# HotFire_BreakoutBoard.net
KiCad netlist of a schematic drawn in EAGLE
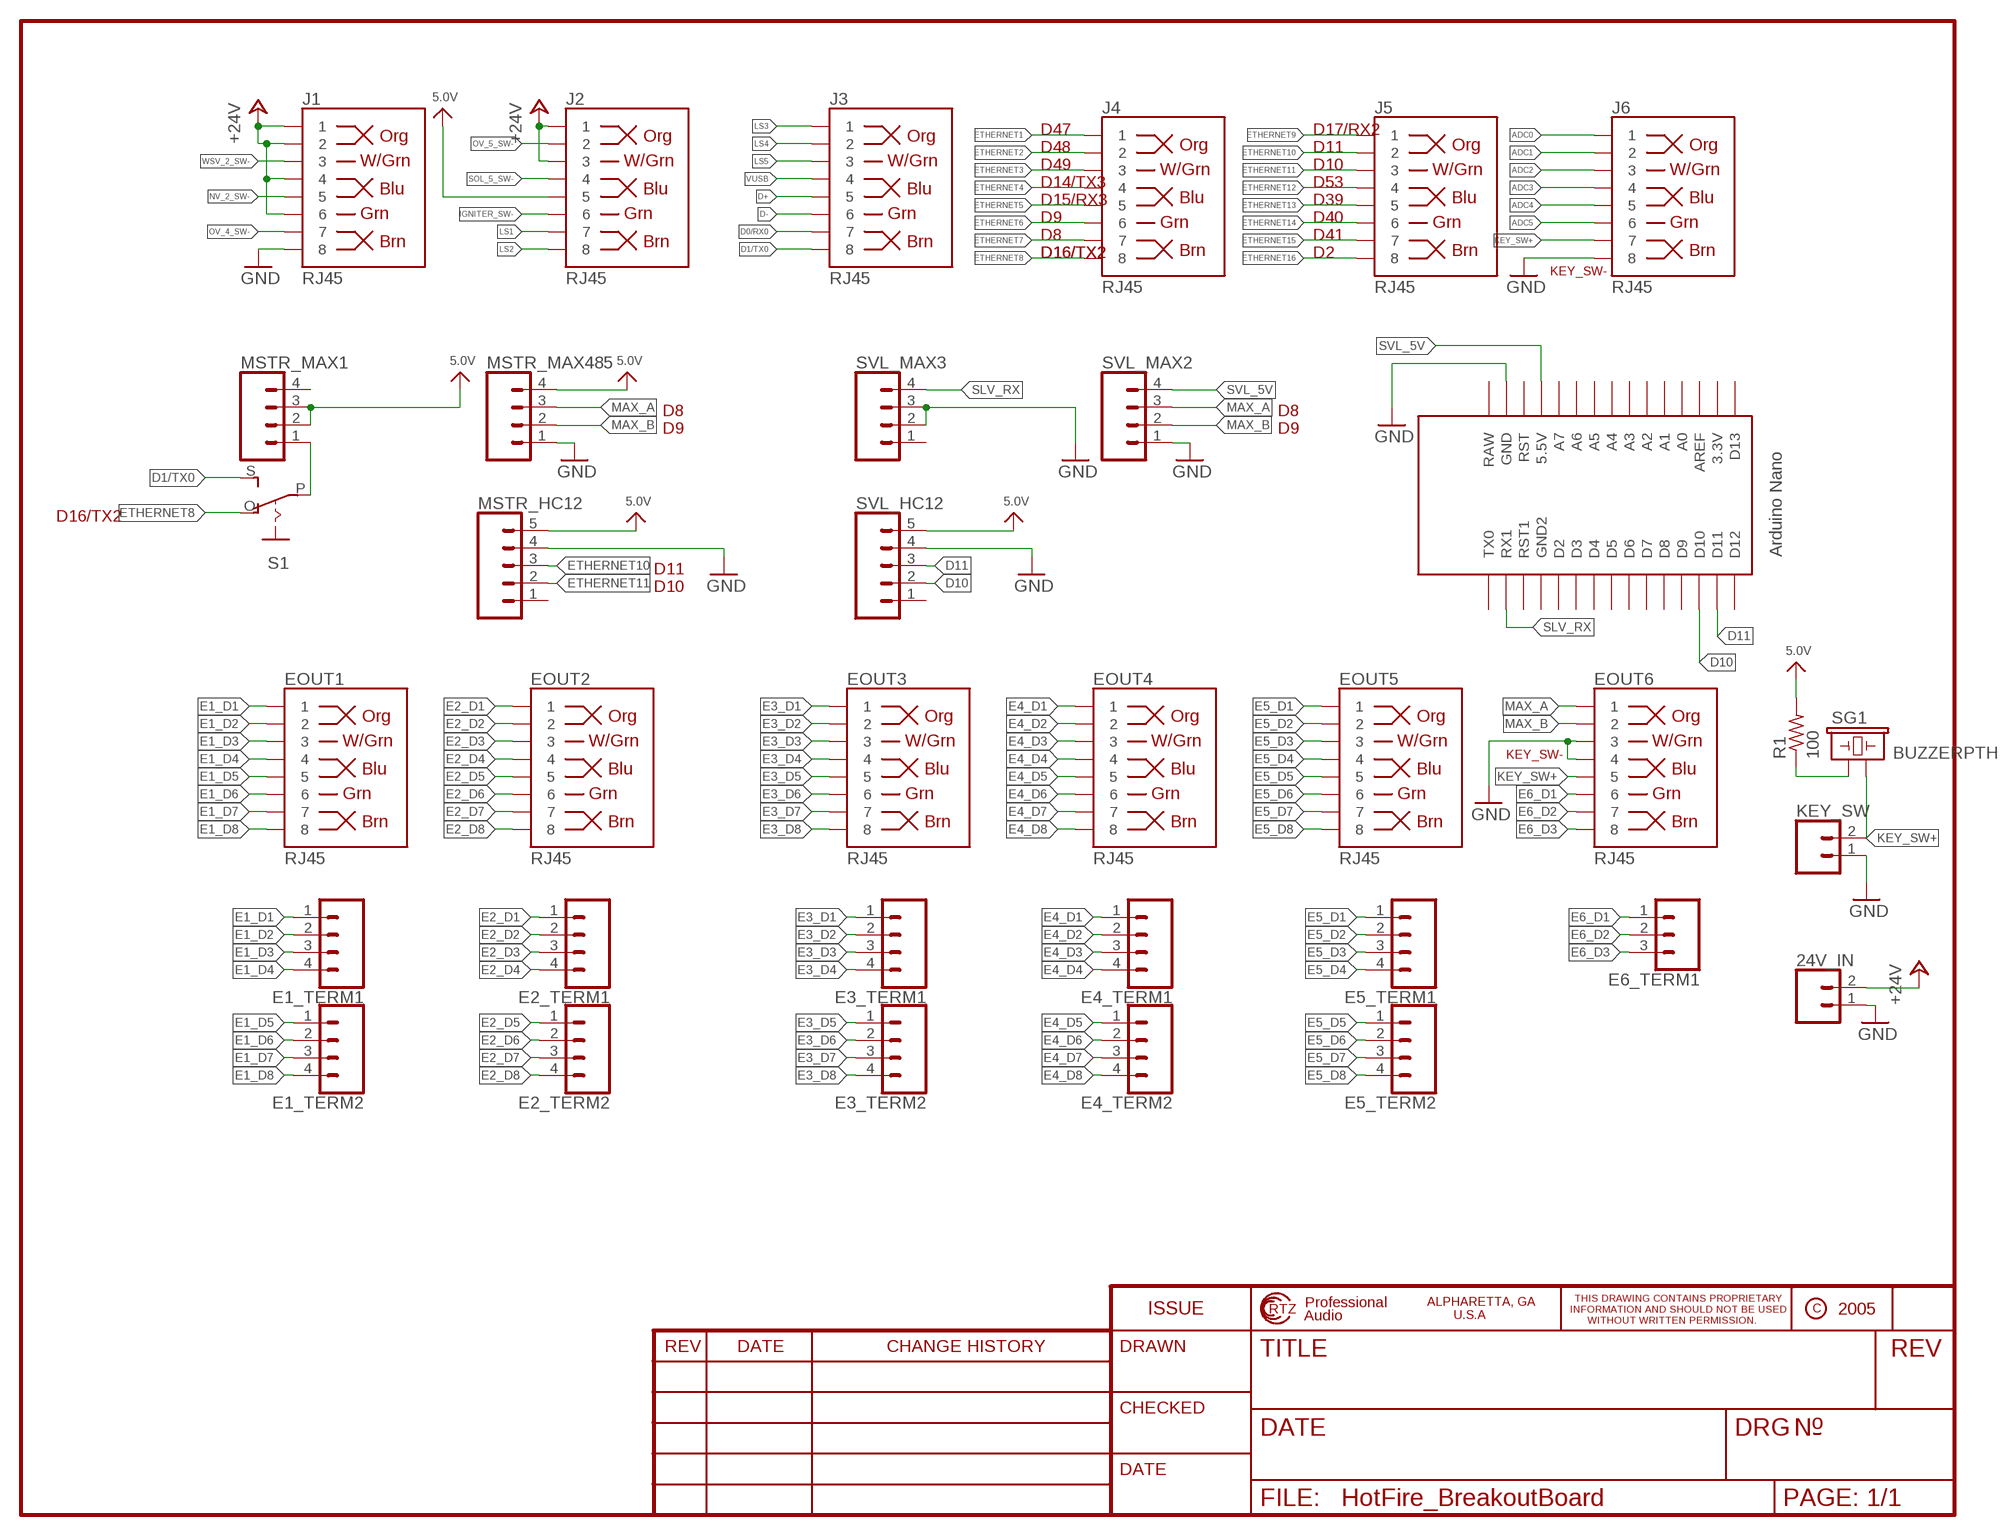
[diagram p0: schematic, sheet 1]

(export (version "E")
  (design (tool "Eeschema 10.0.6"))
  (components
    (comp (ref "24V_IN")
      (value "CONN_023.5MM")
      (footprint "eagle-import:SCREWTERMINAL-3.5MM-2")
      (libsource (lib "eagle-import") (part "CONN_023.5MM"))
    )
    (comp (ref "E1_TERM1")
      (value "CONN_04SCREW")
      (footprint "eagle-import:SCREWTERMINAL-3.5MM-4")
      (libsource (lib "eagle-import") (part "CONN_04SCREW"))
    )
    (comp (ref "E1_TERM2")
      (value "CONN_04SCREW")
      (footprint "eagle-import:SCREWTERMINAL-3.5MM-4")
      (libsource (lib "eagle-import") (part "CONN_04SCREW"))
    )
    (comp (ref "E2_TERM1")
      (value "CONN_04SCREW")
      (footprint "eagle-import:SCREWTERMINAL-3.5MM-4")
      (libsource (lib "eagle-import") (part "CONN_04SCREW"))
    )
    (comp (ref "E2_TERM2")
      (value "CONN_04SCREW")
      (footprint "eagle-import:SCREWTERMINAL-3.5MM-4")
      (libsource (lib "eagle-import") (part "CONN_04SCREW"))
    )
    (comp (ref "E3_TERM1")
      (value "CONN_04SCREW")
      (footprint "eagle-import:SCREWTERMINAL-3.5MM-4")
      (libsource (lib "eagle-import") (part "CONN_04SCREW"))
    )
    (comp (ref "E3_TERM2")
      (value "CONN_04SCREW")
      (footprint "eagle-import:SCREWTERMINAL-3.5MM-4")
      (libsource (lib "eagle-import") (part "CONN_04SCREW"))
    )
    (comp (ref "E4_TERM1")
      (value "CONN_04SCREW")
      (footprint "eagle-import:SCREWTERMINAL-3.5MM-4")
      (libsource (lib "eagle-import") (part "CONN_04SCREW"))
    )
    (comp (ref "E4_TERM2")
      (value "CONN_04SCREW")
      (footprint "eagle-import:SCREWTERMINAL-3.5MM-4")
      (libsource (lib "eagle-import") (part "CONN_04SCREW"))
    )
    (comp (ref "E5_TERM1")
      (value "CONN_04SCREW")
      (footprint "eagle-import:SCREWTERMINAL-3.5MM-4")
      (libsource (lib "eagle-import") (part "CONN_04SCREW"))
    )
    (comp (ref "E5_TERM2")
      (value "CONN_04SCREW")
      (footprint "eagle-import:SCREWTERMINAL-3.5MM-4")
      (libsource (lib "eagle-import") (part "CONN_04SCREW"))
    )
    (comp (ref "E6_TERM1")
      (value "CONN_03SCREW")
      (footprint "eagle-import:SCREWTERMINAL-3.5MM-3")
      (libsource (lib "eagle-import") (part "CONN_03SCREW"))
    )
    (comp (ref "EOUT1")
      (value "RJ45")
      (footprint "eagle-import:RJ45-8")
      (libsource (lib "eagle-import") (part "RJ45-8"))
    )
    (comp (ref "EOUT2")
      (value "RJ45")
      (footprint "eagle-import:RJ45-8")
      (libsource (lib "eagle-import") (part "RJ45-8"))
    )
    (comp (ref "EOUT3")
      (value "RJ45")
      (footprint "eagle-import:RJ45-8")
      (libsource (lib "eagle-import") (part "RJ45-8"))
    )
    (comp (ref "EOUT4")
      (value "RJ45")
      (footprint "eagle-import:RJ45-8")
      (libsource (lib "eagle-import") (part "RJ45-8"))
    )
    (comp (ref "EOUT5")
      (value "RJ45")
      (footprint "eagle-import:RJ45-8")
      (libsource (lib "eagle-import") (part "RJ45-8"))
    )
    (comp (ref "EOUT6")
      (value "RJ45")
      (footprint "eagle-import:RJ45-8")
      (libsource (lib "eagle-import") (part "RJ45-8"))
    )
    (comp (ref "J1")
      (value "RJ45")
      (footprint "eagle-import:RJ45-8")
      (libsource (lib "eagle-import") (part "RJ45-8"))
    )
    (comp (ref "J2")
      (value "RJ45")
      (footprint "eagle-import:RJ45-8")
      (libsource (lib "eagle-import") (part "RJ45-8"))
    )
    (comp (ref "J3")
      (value "RJ45")
      (footprint "eagle-import:RJ45-8")
      (libsource (lib "eagle-import") (part "RJ45-8"))
    )
    (comp (ref "J4")
      (value "RJ45")
      (footprint "eagle-import:RJ45-8")
      (libsource (lib "eagle-import") (part "RJ45-8"))
    )
    (comp (ref "J5")
      (value "RJ45")
      (footprint "eagle-import:RJ45-8")
      (libsource (lib "eagle-import") (part "RJ45-8"))
    )
    (comp (ref "J6")
      (value "RJ45")
      (footprint "eagle-import:RJ45-8")
      (libsource (lib "eagle-import") (part "RJ45-8"))
    )
    (comp (ref "KEY_SW")
      (value "CONN_023.5MM")
      (footprint "eagle-import:SCREWTERMINAL-3.5MM-2")
      (libsource (lib "eagle-import") (part "CONN_023.5MM"))
    )
    (comp (ref "MSTR_HC12")
      (value "CONN_05")
      (footprint "eagle-import:1X05")
      (libsource (lib "eagle-import") (part "CONN_05"))
    )
    (comp (ref "MSTR_MAX1")
      (value "CONN_04")
      (footprint "eagle-import:1X04")
      (libsource (lib "eagle-import") (part "CONN_04"))
    )
    (comp (ref "MSTR_MAX485")
      (value "CONN_04")
      (footprint "eagle-import:1X04")
      (libsource (lib "eagle-import") (part "CONN_04"))
    )
    (comp (ref "R1")
      (value "100")
      (footprint "eagle-import:R0805")
      (libsource (lib "eagle-import") (part "R-US_R0805"))
    )
    (comp (ref "S1")
      (value "EG1218S")
      (footprint "eagle-import:EG1218")
      (libsource (lib "eagle-import") (part "EG1218S"))
    )
    (comp (ref "SG1")
      (value "BUZZERPTH")
      (footprint "eagle-import:BUZZER-12MM")
      (libsource (lib "eagle-import") (part "BUZZERPTH"))
    )
    (comp (ref "SVL_HC12")
      (value "CONN_05")
      (footprint "eagle-import:1X05")
      (libsource (lib "eagle-import") (part "CONN_05"))
    )
    (comp (ref "SVL_MAX2")
      (value "CONN_04")
      (footprint "eagle-import:1X04")
      (libsource (lib "eagle-import") (part "CONN_04"))
    )
    (comp (ref "SVL_MAX3")
      (value "CONN_04")
      (footprint "eagle-import:1X04")
      (libsource (lib "eagle-import") (part "CONN_04"))
    )
    (comp (ref "U$4")
      (value "NANO")
      (footprint "eagle-import:NANO")
      (libsource (lib "eagle-import") (part "NANO"))
    )
  )
  (nets
    (net (code "1") (name "+24V") (class "Default")
      (node (ref "24V_IN") (pin "2") (pinfunction "2_2") (pintype "passive"))
      (node (ref "J1") (pin "1") (pinfunction "1_1") (pintype "bidirectional"))
      (node (ref "J1") (pin "2") (pinfunction "2_2") (pintype "bidirectional"))
      (node (ref "J1") (pin "4") (pinfunction "4_4") (pintype "bidirectional"))
      (node (ref "J1") (pin "6") (pinfunction "6_6") (pintype "bidirectional"))
      (node (ref "J2") (pin "1") (pinfunction "1_1") (pintype "bidirectional"))
      (node (ref "J2") (pin "3") (pinfunction "3_3") (pintype "bidirectional"))
    )
    (net (code "2") (name "5.0V") (class "Default")
      (node (ref "J2") (pin "5") (pinfunction "5_5") (pintype "bidirectional"))
      (node (ref "MSTR_HC12") (pin "5") (pinfunction "5_5") (pintype "passive"))
      (node (ref "MSTR_MAX1") (pin "2") (pinfunction "2_2") (pintype "passive"))
      (node (ref "MSTR_MAX1") (pin "3") (pinfunction "3_3") (pintype "passive"))
      (node (ref "MSTR_MAX485") (pin "4") (pinfunction "4_4") (pintype "passive"))
      (node (ref "R1") (pin "2") (pinfunction "2_2") (pintype "passive"))
      (node (ref "SVL_HC12") (pin "5") (pinfunction "5_5") (pintype "passive"))
    )
    (net (code "3") (name "ADC0") (class "Default")
      (node (ref "J6") (pin "1") (pinfunction "1_1") (pintype "bidirectional"))
    )
    (net (code "4") (name "ADC1") (class "Default")
      (node (ref "J6") (pin "2") (pinfunction "2_2") (pintype "bidirectional"))
    )
    (net (code "5") (name "ADC2") (class "Default")
      (node (ref "J6") (pin "3") (pinfunction "3_3") (pintype "bidirectional"))
    )
    (net (code "6") (name "ADC3") (class "Default")
      (node (ref "J6") (pin "4") (pinfunction "4_4") (pintype "bidirectional"))
    )
    (net (code "7") (name "ADC4") (class "Default")
      (node (ref "J6") (pin "5") (pinfunction "5_5") (pintype "bidirectional"))
    )
    (net (code "8") (name "ADC5") (class "Default")
      (node (ref "J6") (pin "6") (pinfunction "6_6") (pintype "bidirectional"))
    )
    (net (code "9") (name "D+") (class "Default")
      (node (ref "J3") (pin "5") (pinfunction "5_5") (pintype "bidirectional"))
    )
    (net (code "10") (name "D-") (class "Default")
      (node (ref "J3") (pin "6") (pinfunction "6_6") (pintype "bidirectional"))
    )
    (net (code "11") (name "D0{slash}RX0") (class "Default")
      (node (ref "J3") (pin "7") (pinfunction "7_7") (pintype "bidirectional"))
    )
    (net (code "12") (name "D1{slash}TX0") (class "Default")
      (node (ref "J3") (pin "8") (pinfunction "8_8") (pintype "bidirectional"))
      (node (ref "S1") (pin "S") (pinfunction "S_S") (pintype "passive"))
    )
    (net (code "13") (name "D10") (class "Default")
      (node (ref "SVL_HC12") (pin "2") (pinfunction "2_2") (pintype "passive"))
      (node (ref "U$4") (pin "D10") (pinfunction "D10_D10") (pintype "bidirectional"))
    )
    (net (code "14") (name "D11") (class "Default")
      (node (ref "SVL_HC12") (pin "3") (pinfunction "3_3") (pintype "passive"))
      (node (ref "U$4") (pin "D11") (pinfunction "D11_D11") (pintype "bidirectional"))
    )
    (net (code "15") (name "E1_D1") (class "Default")
      (node (ref "E1_TERM1") (pin "1") (pinfunction "1_1") (pintype "passive"))
      (node (ref "EOUT1") (pin "1") (pinfunction "1_1") (pintype "bidirectional"))
    )
    (net (code "16") (name "E1_D2") (class "Default")
      (node (ref "E1_TERM1") (pin "2") (pinfunction "2_2") (pintype "passive"))
      (node (ref "EOUT1") (pin "2") (pinfunction "2_2") (pintype "bidirectional"))
    )
    (net (code "17") (name "E1_D3") (class "Default")
      (node (ref "E1_TERM1") (pin "3") (pinfunction "3_3") (pintype "passive"))
      (node (ref "EOUT1") (pin "3") (pinfunction "3_3") (pintype "bidirectional"))
    )
    (net (code "18") (name "E1_D4") (class "Default")
      (node (ref "E1_TERM1") (pin "4") (pinfunction "4_4") (pintype "passive"))
      (node (ref "EOUT1") (pin "4") (pinfunction "4_4") (pintype "bidirectional"))
    )
    (net (code "19") (name "E1_D5") (class "Default")
      (node (ref "E1_TERM2") (pin "1") (pinfunction "1_1") (pintype "passive"))
      (node (ref "EOUT1") (pin "5") (pinfunction "5_5") (pintype "bidirectional"))
    )
    (net (code "20") (name "E1_D6") (class "Default")
      (node (ref "E1_TERM2") (pin "2") (pinfunction "2_2") (pintype "passive"))
      (node (ref "EOUT1") (pin "6") (pinfunction "6_6") (pintype "bidirectional"))
    )
    (net (code "21") (name "E1_D7") (class "Default")
      (node (ref "E1_TERM2") (pin "3") (pinfunction "3_3") (pintype "passive"))
      (node (ref "EOUT1") (pin "7") (pinfunction "7_7") (pintype "bidirectional"))
    )
    (net (code "22") (name "E1_D8") (class "Default")
      (node (ref "E1_TERM2") (pin "4") (pinfunction "4_4") (pintype "passive"))
      (node (ref "EOUT1") (pin "8") (pinfunction "8_8") (pintype "bidirectional"))
    )
    (net (code "23") (name "E2_D1") (class "Default")
      (node (ref "E2_TERM1") (pin "1") (pinfunction "1_1") (pintype "passive"))
      (node (ref "EOUT2") (pin "1") (pinfunction "1_1") (pintype "bidirectional"))
    )
    (net (code "24") (name "E2_D2") (class "Default")
      (node (ref "E2_TERM1") (pin "2") (pinfunction "2_2") (pintype "passive"))
      (node (ref "EOUT2") (pin "2") (pinfunction "2_2") (pintype "bidirectional"))
    )
    (net (code "25") (name "E2_D3") (class "Default")
      (node (ref "E2_TERM1") (pin "3") (pinfunction "3_3") (pintype "passive"))
      (node (ref "EOUT2") (pin "3") (pinfunction "3_3") (pintype "bidirectional"))
    )
    (net (code "26") (name "E2_D4") (class "Default")
      (node (ref "E2_TERM1") (pin "4") (pinfunction "4_4") (pintype "passive"))
      (node (ref "EOUT2") (pin "4") (pinfunction "4_4") (pintype "bidirectional"))
    )
    (net (code "27") (name "E2_D5") (class "Default")
      (node (ref "E2_TERM2") (pin "1") (pinfunction "1_1") (pintype "passive"))
      (node (ref "EOUT2") (pin "5") (pinfunction "5_5") (pintype "bidirectional"))
    )
    (net (code "28") (name "E2_D6") (class "Default")
      (node (ref "E2_TERM2") (pin "2") (pinfunction "2_2") (pintype "passive"))
      (node (ref "EOUT2") (pin "6") (pinfunction "6_6") (pintype "bidirectional"))
    )
    (net (code "29") (name "E2_D7") (class "Default")
      (node (ref "E2_TERM2") (pin "3") (pinfunction "3_3") (pintype "passive"))
      (node (ref "EOUT2") (pin "7") (pinfunction "7_7") (pintype "bidirectional"))
    )
    (net (code "30") (name "E2_D8") (class "Default")
      (node (ref "E2_TERM2") (pin "4") (pinfunction "4_4") (pintype "passive"))
      (node (ref "EOUT2") (pin "8") (pinfunction "8_8") (pintype "bidirectional"))
    )
    (net (code "31") (name "E3_D1") (class "Default")
      (node (ref "E3_TERM1") (pin "1") (pinfunction "1_1") (pintype "passive"))
      (node (ref "EOUT3") (pin "1") (pinfunction "1_1") (pintype "bidirectional"))
    )
    (net (code "32") (name "E3_D2") (class "Default")
      (node (ref "E3_TERM1") (pin "2") (pinfunction "2_2") (pintype "passive"))
      (node (ref "EOUT3") (pin "2") (pinfunction "2_2") (pintype "bidirectional"))
    )
    (net (code "33") (name "E3_D3") (class "Default")
      (node (ref "E3_TERM1") (pin "3") (pinfunction "3_3") (pintype "passive"))
      (node (ref "EOUT3") (pin "3") (pinfunction "3_3") (pintype "bidirectional"))
    )
    (net (code "34") (name "E3_D4") (class "Default")
      (node (ref "E3_TERM1") (pin "4") (pinfunction "4_4") (pintype "passive"))
      (node (ref "EOUT3") (pin "4") (pinfunction "4_4") (pintype "bidirectional"))
    )
    (net (code "35") (name "E3_D5") (class "Default")
      (node (ref "E3_TERM2") (pin "1") (pinfunction "1_1") (pintype "passive"))
      (node (ref "EOUT3") (pin "5") (pinfunction "5_5") (pintype "bidirectional"))
    )
    (net (code "36") (name "E3_D6") (class "Default")
      (node (ref "E3_TERM2") (pin "2") (pinfunction "2_2") (pintype "passive"))
      (node (ref "EOUT3") (pin "6") (pinfunction "6_6") (pintype "bidirectional"))
    )
    (net (code "37") (name "E3_D7") (class "Default")
      (node (ref "E3_TERM2") (pin "3") (pinfunction "3_3") (pintype "passive"))
      (node (ref "EOUT3") (pin "7") (pinfunction "7_7") (pintype "bidirectional"))
    )
    (net (code "38") (name "E3_D8") (class "Default")
      (node (ref "E3_TERM2") (pin "4") (pinfunction "4_4") (pintype "passive"))
      (node (ref "EOUT3") (pin "8") (pinfunction "8_8") (pintype "bidirectional"))
    )
    (net (code "39") (name "E4_D1") (class "Default")
      (node (ref "E4_TERM1") (pin "1") (pinfunction "1_1") (pintype "passive"))
      (node (ref "EOUT4") (pin "1") (pinfunction "1_1") (pintype "bidirectional"))
    )
    (net (code "40") (name "E4_D2") (class "Default")
      (node (ref "E4_TERM1") (pin "2") (pinfunction "2_2") (pintype "passive"))
      (node (ref "EOUT4") (pin "2") (pinfunction "2_2") (pintype "bidirectional"))
    )
    (net (code "41") (name "E4_D3") (class "Default")
      (node (ref "E4_TERM1") (pin "3") (pinfunction "3_3") (pintype "passive"))
      (node (ref "EOUT4") (pin "3") (pinfunction "3_3") (pintype "bidirectional"))
    )
    (net (code "42") (name "E4_D4") (class "Default")
      (node (ref "E4_TERM1") (pin "4") (pinfunction "4_4") (pintype "passive"))
      (node (ref "EOUT4") (pin "4") (pinfunction "4_4") (pintype "bidirectional"))
    )
    (net (code "43") (name "E4_D5") (class "Default")
      (node (ref "E4_TERM2") (pin "1") (pinfunction "1_1") (pintype "passive"))
      (node (ref "EOUT4") (pin "5") (pinfunction "5_5") (pintype "bidirectional"))
    )
    (net (code "44") (name "E4_D6") (class "Default")
      (node (ref "E4_TERM2") (pin "2") (pinfunction "2_2") (pintype "passive"))
      (node (ref "EOUT4") (pin "6") (pinfunction "6_6") (pintype "bidirectional"))
    )
    (net (code "45") (name "E4_D7") (class "Default")
      (node (ref "E4_TERM2") (pin "3") (pinfunction "3_3") (pintype "passive"))
      (node (ref "EOUT4") (pin "7") (pinfunction "7_7") (pintype "bidirectional"))
    )
    (net (code "46") (name "E4_D8") (class "Default")
      (node (ref "E4_TERM2") (pin "4") (pinfunction "4_4") (pintype "passive"))
      (node (ref "EOUT4") (pin "8") (pinfunction "8_8") (pintype "bidirectional"))
    )
    (net (code "47") (name "E5_D1") (class "Default")
      (node (ref "E5_TERM1") (pin "1") (pinfunction "1_1") (pintype "passive"))
      (node (ref "EOUT5") (pin "1") (pinfunction "1_1") (pintype "bidirectional"))
    )
    (net (code "48") (name "E5_D2") (class "Default")
      (node (ref "E5_TERM1") (pin "2") (pinfunction "2_2") (pintype "passive"))
      (node (ref "EOUT5") (pin "2") (pinfunction "2_2") (pintype "bidirectional"))
    )
    (net (code "49") (name "E5_D3") (class "Default")
      (node (ref "E5_TERM1") (pin "3") (pinfunction "3_3") (pintype "passive"))
      (node (ref "EOUT5") (pin "3") (pinfunction "3_3") (pintype "bidirectional"))
    )
    (net (code "50") (name "E5_D4") (class "Default")
      (node (ref "E5_TERM1") (pin "4") (pinfunction "4_4") (pintype "passive"))
      (node (ref "EOUT5") (pin "4") (pinfunction "4_4") (pintype "bidirectional"))
    )
    (net (code "51") (name "E5_D5") (class "Default")
      (node (ref "E5_TERM2") (pin "1") (pinfunction "1_1") (pintype "passive"))
      (node (ref "EOUT5") (pin "5") (pinfunction "5_5") (pintype "bidirectional"))
    )
    (net (code "52") (name "E5_D6") (class "Default")
      (node (ref "E5_TERM2") (pin "2") (pinfunction "2_2") (pintype "passive"))
      (node (ref "EOUT5") (pin "6") (pinfunction "6_6") (pintype "bidirectional"))
    )
    (net (code "53") (name "E5_D7") (class "Default")
      (node (ref "E5_TERM2") (pin "3") (pinfunction "3_3") (pintype "passive"))
      (node (ref "EOUT5") (pin "7") (pinfunction "7_7") (pintype "bidirectional"))
    )
    (net (code "54") (name "E5_D8") (class "Default")
      (node (ref "E5_TERM2") (pin "4") (pinfunction "4_4") (pintype "passive"))
      (node (ref "EOUT5") (pin "8") (pinfunction "8_8") (pintype "bidirectional"))
    )
    (net (code "55") (name "E6_D1") (class "Default")
      (node (ref "E6_TERM1") (pin "1") (pinfunction "1_1") (pintype "passive"))
      (node (ref "EOUT6") (pin "6") (pinfunction "6_6") (pintype "bidirectional"))
    )
    (net (code "56") (name "E6_D2") (class "Default")
      (node (ref "E6_TERM1") (pin "2") (pinfunction "2_2") (pintype "passive"))
      (node (ref "EOUT6") (pin "7") (pinfunction "7_7") (pintype "bidirectional"))
    )
    (net (code "57") (name "E6_D3") (class "Default")
      (node (ref "E6_TERM1") (pin "3") (pinfunction "3_3") (pintype "passive"))
      (node (ref "EOUT6") (pin "8") (pinfunction "8_8") (pintype "bidirectional"))
    )
    (net (code "58") (name "ETHERNET1") (class "Default")
      (node (ref "J4") (pin "1") (pinfunction "1_1") (pintype "bidirectional"))
    )
    (net (code "59") (name "ETHERNET2") (class "Default")
      (node (ref "J4") (pin "2") (pinfunction "2_2") (pintype "bidirectional"))
    )
    (net (code "60") (name "ETHERNET3") (class "Default")
      (node (ref "J4") (pin "3") (pinfunction "3_3") (pintype "bidirectional"))
    )
    (net (code "61") (name "ETHERNET4") (class "Default")
      (node (ref "J4") (pin "4") (pinfunction "4_4") (pintype "bidirectional"))
    )
    (net (code "62") (name "ETHERNET5") (class "Default")
      (node (ref "J4") (pin "5") (pinfunction "5_5") (pintype "bidirectional"))
    )
    (net (code "63") (name "ETHERNET6") (class "Default")
      (node (ref "J4") (pin "6") (pinfunction "6_6") (pintype "bidirectional"))
    )
    (net (code "64") (name "ETHERNET7") (class "Default")
      (node (ref "J4") (pin "7") (pinfunction "7_7") (pintype "bidirectional"))
    )
    (net (code "65") (name "ETHERNET8") (class "Default")
      (node (ref "J4") (pin "8") (pinfunction "8_8") (pintype "bidirectional"))
      (node (ref "S1") (pin "O") (pinfunction "O_O") (pintype "passive"))
    )
    (net (code "66") (name "ETHERNET9") (class "Default")
      (node (ref "J5") (pin "1") (pinfunction "1_1") (pintype "bidirectional"))
    )
    (net (code "67") (name "ETHERNET10") (class "Default")
      (node (ref "J5") (pin "2") (pinfunction "2_2") (pintype "bidirectional"))
      (node (ref "MSTR_HC12") (pin "3") (pinfunction "3_3") (pintype "passive"))
    )
    (net (code "68") (name "ETHERNET11") (class "Default")
      (node (ref "J5") (pin "3") (pinfunction "3_3") (pintype "bidirectional"))
      (node (ref "MSTR_HC12") (pin "2") (pinfunction "2_2") (pintype "passive"))
    )
    (net (code "69") (name "ETHERNET12") (class "Default")
      (node (ref "J5") (pin "4") (pinfunction "4_4") (pintype "bidirectional"))
    )
    (net (code "70") (name "ETHERNET13") (class "Default")
      (node (ref "J5") (pin "5") (pinfunction "5_5") (pintype "bidirectional"))
    )
    (net (code "71") (name "ETHERNET14") (class "Default")
      (node (ref "J5") (pin "6") (pinfunction "6_6") (pintype "bidirectional"))
    )
    (net (code "72") (name "ETHERNET15") (class "Default")
      (node (ref "J5") (pin "7") (pinfunction "7_7") (pintype "bidirectional"))
    )
    (net (code "73") (name "ETHERNET16") (class "Default")
      (node (ref "J5") (pin "8") (pinfunction "8_8") (pintype "bidirectional"))
    )
    (net (code "74") (name "GND") (class "Default")
      (node (ref "24V_IN") (pin "1") (pinfunction "1_1") (pintype "passive"))
      (node (ref "EOUT6") (pin "3") (pinfunction "3_3") (pintype "bidirectional"))
      (node (ref "EOUT6") (pin "4") (pinfunction "4_4") (pintype "bidirectional"))
      (node (ref "J1") (pin "8") (pinfunction "8_8") (pintype "bidirectional"))
      (node (ref "J6") (pin "8") (pinfunction "8_8") (pintype "bidirectional"))
      (node (ref "KEY_SW") (pin "1") (pinfunction "1_1") (pintype "passive"))
      (node (ref "MSTR_HC12") (pin "4") (pinfunction "4_4") (pintype "passive"))
      (node (ref "MSTR_MAX485") (pin "1") (pinfunction "1_1") (pintype "passive"))
      (node (ref "SVL_HC12") (pin "4") (pinfunction "4_4") (pintype "passive"))
      (node (ref "SVL_MAX2") (pin "1") (pinfunction "1_1") (pintype "passive"))
      (node (ref "SVL_MAX3") (pin "2") (pinfunction "2_2") (pintype "passive"))
      (node (ref "SVL_MAX3") (pin "3") (pinfunction "3_3") (pintype "passive"))
      (node (ref "U$4") (pin "GND") (pinfunction "GND_GND") (pintype "bidirectional"))
    )
    (net (code "75") (name "IGNITER_SW-") (class "Default")
      (node (ref "J2") (pin "6") (pinfunction "6_6") (pintype "bidirectional"))
    )
    (net (code "76") (name "KEY_SW+") (class "Default")
      (node (ref "EOUT6") (pin "5") (pinfunction "5_5") (pintype "bidirectional"))
      (node (ref "J6") (pin "7") (pinfunction "7_7") (pintype "bidirectional"))
      (node (ref "KEY_SW") (pin "2") (pinfunction "2_2") (pintype "passive"))
      (node (ref "SG1") (pin "-") (pinfunction "2_-") (pintype "passive"))
    )
    (net (code "77") (name "LS1") (class "Default")
      (node (ref "J2") (pin "7") (pinfunction "7_7") (pintype "bidirectional"))
    )
    (net (code "78") (name "LS2") (class "Default")
      (node (ref "J2") (pin "8") (pinfunction "8_8") (pintype "bidirectional"))
    )
    (net (code "79") (name "LS3") (class "Default")
      (node (ref "J3") (pin "1") (pinfunction "1_1") (pintype "bidirectional"))
    )
    (net (code "80") (name "LS4") (class "Default")
      (node (ref "J3") (pin "2") (pinfunction "2_2") (pintype "bidirectional"))
    )
    (net (code "81") (name "LS5") (class "Default")
      (node (ref "J3") (pin "3") (pinfunction "3_3") (pintype "bidirectional"))
    )
    (net (code "82") (name "MAX_A") (class "Default")
      (node (ref "EOUT6") (pin "1") (pinfunction "1_1") (pintype "bidirectional"))
      (node (ref "MSTR_MAX485") (pin "3") (pinfunction "3_3") (pintype "passive"))
      (node (ref "SVL_MAX2") (pin "3") (pinfunction "3_3") (pintype "passive"))
    )
    (net (code "83") (name "MAX_B") (class "Default")
      (node (ref "EOUT6") (pin "2") (pinfunction "2_2") (pintype "bidirectional"))
      (node (ref "MSTR_MAX485") (pin "2") (pinfunction "2_2") (pintype "passive"))
      (node (ref "SVL_MAX2") (pin "2") (pinfunction "2_2") (pintype "passive"))
    )
    (net (code "84") (name "NV_2_SW-") (class "Default")
      (node (ref "J1") (pin "5") (pinfunction "5_5") (pintype "bidirectional"))
    )
    (net (code "85") (name "Net-(MSTR_MAX1-Pad1)") (class "Default")
      (node (ref "MSTR_MAX1") (pin "1") (pinfunction "1_1") (pintype "passive"))
      (node (ref "S1") (pin "P") (pinfunction "P_P") (pintype "passive"))
    )
    (net (code "86") (name "Net-(SG1-1)") (class "Default")
      (node (ref "R1") (pin "1") (pinfunction "1_1") (pintype "passive"))
      (node (ref "SG1") (pin "+") (pinfunction "1_+") (pintype "passive"))
    )
    (net (code "87") (name "OV_4_SW-") (class "Default")
      (node (ref "J1") (pin "7") (pinfunction "7_7") (pintype "bidirectional"))
    )
    (net (code "88") (name "OV_5_SW-") (class "Default")
      (node (ref "J2") (pin "2") (pinfunction "2_2") (pintype "bidirectional"))
    )
    (net (code "89") (name "SLV_RX") (class "Default")
      (node (ref "SVL_MAX3") (pin "4") (pinfunction "4_4") (pintype "passive"))
      (node (ref "U$4") (pin "RX1") (pinfunction "RX1_RX1") (pintype "bidirectional"))
    )
    (net (code "90") (name "SOL_5_SW-") (class "Default")
      (node (ref "J2") (pin "4") (pinfunction "4_4") (pintype "bidirectional"))
    )
    (net (code "91") (name "SVL_5V") (class "Default")
      (node (ref "SVL_MAX2") (pin "4") (pinfunction "4_4") (pintype "passive"))
      (node (ref "U$4") (pin "5V") (pinfunction "5.5V_5V") (pintype "bidirectional"))
    )
    (net (code "92") (name "VUSB") (class "Default")
      (node (ref "J3") (pin "4") (pinfunction "4_4") (pintype "bidirectional"))
    )
    (net (code "93") (name "WSV_2_SW-") (class "Default")
      (node (ref "J1") (pin "3") (pinfunction "3_3") (pintype "bidirectional"))
    )
    (net (code "94") (name "unconnected-(MSTR_HC12-Pad1)") (class "Default")
      (node (ref "MSTR_HC12") (pin "1") (pinfunction "1_1") (pintype "passive"))
    )
    (net (code "95") (name "unconnected-(MSTR_MAX1-Pad4)") (class "Default")
      (node (ref "MSTR_MAX1") (pin "4") (pinfunction "4_4") (pintype "passive"))
    )
    (net (code "96") (name "unconnected-(SVL_HC12-Pad1)") (class "Default")
      (node (ref "SVL_HC12") (pin "1") (pinfunction "1_1") (pintype "passive"))
    )
    (net (code "97") (name "unconnected-(SVL_MAX3-Pad1)") (class "Default")
      (node (ref "SVL_MAX3") (pin "1") (pinfunction "1_1") (pintype "passive"))
    )
    (net (code "98") (name "unconnected-(U$4-GND2-PadGND1)") (class "Default")
      (node (ref "U$4") (pin "GND1") (pinfunction "GND2_GND1") (pintype "bidirectional"))
    )
    (net (code "99") (name "unconnected-(U$4-Pad3.3V)") (class "Default")
      (node (ref "U$4") (pin "3.3V") (pinfunction "3.3V_3.3V") (pintype "bidirectional"))
    )
    (net (code "100") (name "unconnected-(U$4-PadA0)") (class "Default")
      (node (ref "U$4") (pin "A0") (pinfunction "A0_A0") (pintype "bidirectional"))
    )
    (net (code "101") (name "unconnected-(U$4-PadA1)") (class "Default")
      (node (ref "U$4") (pin "A1") (pinfunction "A1_A1") (pintype "bidirectional"))
    )
    (net (code "102") (name "unconnected-(U$4-PadA2)") (class "Default")
      (node (ref "U$4") (pin "A2") (pinfunction "A2_A2") (pintype "bidirectional"))
    )
    (net (code "103") (name "unconnected-(U$4-PadA3)") (class "Default")
      (node (ref "U$4") (pin "A3") (pinfunction "A3_A3") (pintype "bidirectional"))
    )
    (net (code "104") (name "unconnected-(U$4-PadA4)") (class "Default")
      (node (ref "U$4") (pin "A4") (pinfunction "A4_A4") (pintype "bidirectional"))
    )
    (net (code "105") (name "unconnected-(U$4-PadA5)") (class "Default")
      (node (ref "U$4") (pin "A5") (pinfunction "A5_A5") (pintype "bidirectional"))
    )
    (net (code "106") (name "unconnected-(U$4-PadA6)") (class "Default")
      (node (ref "U$4") (pin "A6") (pinfunction "A6_A6") (pintype "bidirectional"))
    )
    (net (code "107") (name "unconnected-(U$4-PadA7)") (class "Default")
      (node (ref "U$4") (pin "A7") (pinfunction "A7_A7") (pintype "bidirectional"))
    )
    (net (code "108") (name "unconnected-(U$4-PadAREF)") (class "Default")
      (node (ref "U$4") (pin "AREF") (pinfunction "AREF_AREF") (pintype "bidirectional"))
    )
    (net (code "109") (name "unconnected-(U$4-PadD2)") (class "Default")
      (node (ref "U$4") (pin "D2") (pinfunction "D2_D2") (pintype "bidirectional"))
    )
    (net (code "110") (name "unconnected-(U$4-PadD3)") (class "Default")
      (node (ref "U$4") (pin "D3") (pinfunction "D3_D3") (pintype "bidirectional"))
    )
    (net (code "111") (name "unconnected-(U$4-PadD4)") (class "Default")
      (node (ref "U$4") (pin "D4") (pinfunction "D4_D4") (pintype "bidirectional"))
    )
    (net (code "112") (name "unconnected-(U$4-PadD5)") (class "Default")
      (node (ref "U$4") (pin "D5") (pinfunction "D5_D5") (pintype "bidirectional"))
    )
    (net (code "113") (name "unconnected-(U$4-PadD6)") (class "Default")
      (node (ref "U$4") (pin "D6") (pinfunction "D6_D6") (pintype "bidirectional"))
    )
    (net (code "114") (name "unconnected-(U$4-PadD7)") (class "Default")
      (node (ref "U$4") (pin "D7") (pinfunction "D7_D7") (pintype "bidirectional"))
    )
    (net (code "115") (name "unconnected-(U$4-PadD8)") (class "Default")
      (node (ref "U$4") (pin "D8") (pinfunction "D8_D8") (pintype "bidirectional"))
    )
    (net (code "116") (name "unconnected-(U$4-PadD9)") (class "Default")
      (node (ref "U$4") (pin "D9") (pinfunction "D9_D9") (pintype "bidirectional"))
    )
    (net (code "117") (name "unconnected-(U$4-PadD12)") (class "Default")
      (node (ref "U$4") (pin "D12") (pinfunction "D12_D12") (pintype "bidirectional"))
    )
    (net (code "118") (name "unconnected-(U$4-PadD13)") (class "Default")
      (node (ref "U$4") (pin "D13") (pinfunction "D13_D13") (pintype "bidirectional"))
    )
    (net (code "119") (name "unconnected-(U$4-PadICSP1)") (class "Default")
      (node (ref "U$4") (pin "ICSP1") (pinfunction "ICSP1_ICSP1") (pintype "bidirectional"))
    )
    (net (code "120") (name "unconnected-(U$4-PadICSP2)") (class "Default")
      (node (ref "U$4") (pin "ICSP2") (pinfunction "ICSP2_ICSP2") (pintype "bidirectional"))
    )
    (net (code "121") (name "unconnected-(U$4-PadICSP3)") (class "Default")
      (node (ref "U$4") (pin "ICSP3") (pinfunction "ICSP3_ICSP3") (pintype "bidirectional"))
    )
    (net (code "122") (name "unconnected-(U$4-PadICSP4)") (class "Default")
      (node (ref "U$4") (pin "ICSP4") (pinfunction "ICSP4_ICSP4") (pintype "bidirectional"))
    )
    (net (code "123") (name "unconnected-(U$4-PadICSP5)") (class "Default")
      (node (ref "U$4") (pin "ICSP5") (pinfunction "ICSP5_ICSP5") (pintype "bidirectional"))
    )
    (net (code "124") (name "unconnected-(U$4-PadICSP6)") (class "Default")
      (node (ref "U$4") (pin "ICSP6") (pinfunction "ICSP6_ICSP6") (pintype "bidirectional"))
    )
    (net (code "125") (name "unconnected-(U$4-PadRAW)") (class "Default")
      (node (ref "U$4") (pin "RAW") (pinfunction "RAW_RAW") (pintype "bidirectional"))
    )
    (net (code "126") (name "unconnected-(U$4-PadRST)") (class "Default")
      (node (ref "U$4") (pin "RST") (pinfunction "RST_RST") (pintype "bidirectional"))
    )
    (net (code "127") (name "unconnected-(U$4-PadRST1)") (class "Default")
      (node (ref "U$4") (pin "RST1") (pinfunction "RST1_RST1") (pintype "bidirectional"))
    )
    (net (code "128") (name "unconnected-(U$4-PadTX0)") (class "Default")
      (node (ref "U$4") (pin "TX0") (pinfunction "TX0_TX0") (pintype "bidirectional"))
    )
  )
)
